# VoltageAmplifier.net
KiCad netlist of a schematic drawn in Altium Designer
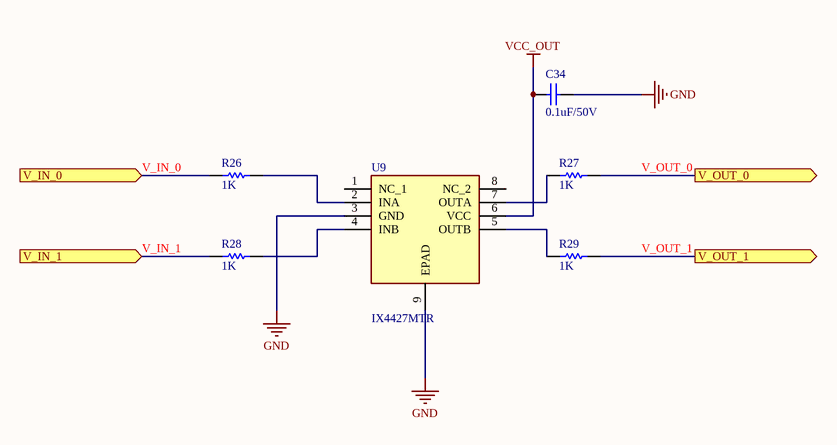
[diagram p0: VoltageAmplifier.SchDoc]

(export (version "E")
  (design (tool "Eeschema 10.0.6"))
  (components
    (comp (ref "C34")
      (value "0.1uF/50V")
      (footprint "RAD-0.3")
      (description "Capacitor")
      (fields (field (name "PUBLISHER") "Altium Limited"))
      (libsource (lib "Miscellaneous Devices") (part "Cap"))
    )
    (comp (ref "R26")
      (value "1K")
      (footprint "AXIAL-0.3")
      (description "Resistor")
      (fields (field (name "PUBLISHER") "Altium Limited"))
      (libsource (lib "Miscellaneous Devices") (part "Res1"))
    )
    (comp (ref "R27")
      (value "1K")
      (footprint "AXIAL-0.3")
      (description "Resistor")
      (fields (field (name "PUBLISHER") "Altium Limited"))
      (libsource (lib "Miscellaneous Devices") (part "Res1"))
    )
    (comp (ref "R28")
      (value "1K")
      (footprint "AXIAL-0.3")
      (description "Resistor")
      (fields (field (name "PUBLISHER") "Altium Limited"))
      (libsource (lib "Miscellaneous Devices") (part "Res1"))
    )
    (comp (ref "R29")
      (value "1K")
      (footprint "AXIAL-0.3")
      (description "Resistor")
      (fields (field (name "PUBLISHER") "Altium Limited"))
      (libsource (lib "Miscellaneous Devices") (part "Res1"))
    )
    (comp (ref "U9")
      (value "IX4427MTR")
      (footprint "SamacSys:SON65P300X300X90-9N")
      (description "Integrated Circuit")
      (fields (field (name "MOUSER PART NUMBER") "849-IX4427MTR"))
      (libsource (lib "*") (part "IX4427MTR"))
    )
  )
  (nets
    (net (code "1") (name "/V_IN_0") (class "Default")
      (node (ref "R26") (pin "1") (pinfunction "1_1") (pintype "passive"))
    )
    (net (code "2") (name "/V_IN_1") (class "Default")
      (node (ref "R28") (pin "1") (pinfunction "1_1") (pintype "passive"))
    )
    (net (code "3") (name "/V_OUT_0") (class "Default")
      (node (ref "R27") (pin "2") (pinfunction "2_2") (pintype "passive"))
    )
    (net (code "4") (name "/V_OUT_1") (class "Default")
      (node (ref "R29") (pin "2") (pinfunction "2_2") (pintype "passive"))
    )
    (net (code "5") (name "GND") (class "Default")
      (node (ref "C34") (pin "2") (pinfunction "2_2") (pintype "passive"))
      (node (ref "U9") (pin "3") (pinfunction "GND_3") (pintype "passive"))
      (node (ref "U9") (pin "9") (pinfunction "EPAD_9") (pintype "passive"))
    )
    (net (code "6") (name "Net-(U9-INA)") (class "Default")
      (node (ref "R26") (pin "2") (pinfunction "2_2") (pintype "passive"))
      (node (ref "U9") (pin "2") (pinfunction "INA_2") (pintype "passive"))
    )
    (net (code "7") (name "Net-(U9-INB)") (class "Default")
      (node (ref "R28") (pin "2") (pinfunction "2_2") (pintype "passive"))
      (node (ref "U9") (pin "4") (pinfunction "INB_4") (pintype "passive"))
    )
    (net (code "8") (name "Net-(U9-OUTA)") (class "Default")
      (node (ref "R27") (pin "1") (pinfunction "1_1") (pintype "passive"))
      (node (ref "U9") (pin "7") (pinfunction "OUTA_7") (pintype "passive"))
    )
    (net (code "9") (name "Net-(U9-OUTB)") (class "Default")
      (node (ref "R29") (pin "1") (pinfunction "1_1") (pintype "passive"))
      (node (ref "U9") (pin "5") (pinfunction "OUTB_5") (pintype "passive"))
    )
    (net (code "10") (name "VCC_OUT") (class "Default")
      (node (ref "C34") (pin "1") (pinfunction "1_1") (pintype "passive"))
      (node (ref "U9") (pin "6") (pinfunction "VCC_6") (pintype "passive"))
    )
    (net (code "11") (name "unconnected-(U9-NC_1-Pad1)") (class "Default")
      (node (ref "U9") (pin "1") (pinfunction "NC_1_1") (pintype "passive"))
    )
    (net (code "12") (name "unconnected-(U9-NC_2-Pad8)") (class "Default")
      (node (ref "U9") (pin "8") (pinfunction "NC_2_8") (pintype "passive"))
    )
  )
)
